# arduino-ss-usbmod-zif.net
KiCad netlist of a schematic drawn in EAGLE
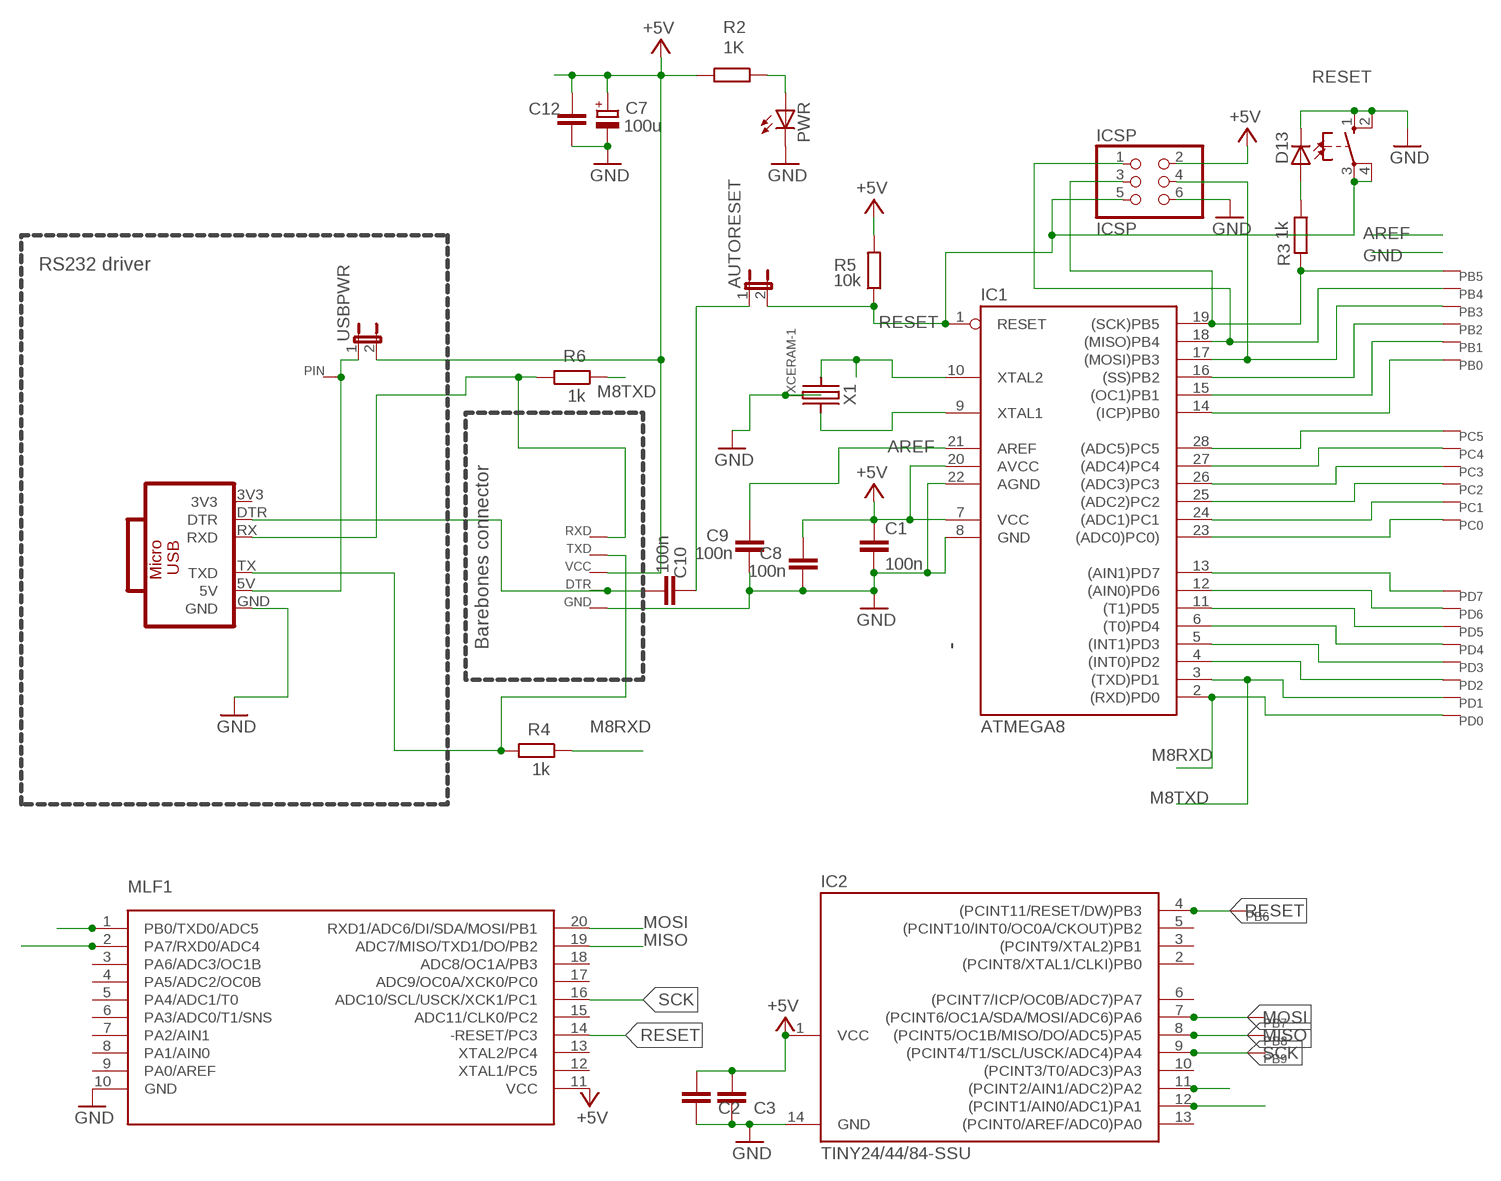
[diagram p0: schematic, sheet 1]

(export (version "E")
  (design (tool "Eeschema 10.0.6"))
  (components
    (comp (ref "AUTORESET")
      (value "JUMPER-2PTH")
      (footprint "eagle-import:1X02")
      (libsource (lib "eagle-import") (part "JUMPER-2PTH"))
    )
    (comp (ref "C1")
      (value "100n")
      (footprint "eagle-import:C050-025X075")
      (libsource (lib "eagle-import") (part "C-EU050-025X075"))
    )
    (comp (ref "C2")
      (value "100n")
      (footprint "eagle-import:C050-025X075")
      (libsource (lib "eagle-import") (part "C-EU050-025X075"))
    )
    (comp (ref "C3")
      (value "100n")
      (footprint "eagle-import:C1812")
      (libsource (lib "eagle-import") (part "C-EUC1812"))
    )
    (comp (ref "C7")
      (value "100u")
      (footprint "eagle-import:E3,5-8")
      (libsource (lib "eagle-import") (part "CPOL-EUE3.5-8"))
    )
    (comp (ref "C8")
      (value "100n")
      (footprint "eagle-import:C050-025X075")
      (libsource (lib "eagle-import") (part "C-EU050-025X075"))
    )
    (comp (ref "C9")
      (value "100n")
      (footprint "eagle-import:C050-025X075")
      (libsource (lib "eagle-import") (part "C-EU050-025X075"))
    )
    (comp (ref "C10")
      (value "100n")
      (footprint "eagle-import:C050-025X075")
      (libsource (lib "eagle-import") (part "C-EU050-025X075"))
    )
    (comp (ref "C12")
      (value "100n")
      (footprint "eagle-import:C050-025X075")
      (libsource (lib "eagle-import") (part "C-EU050-025X075"))
    )
    (comp (ref "D13")
      (value "LED3MM")
      (footprint "eagle-import:LED3MM")
      (libsource (lib "eagle-import") (part "LED3MM"))
    )
    (comp (ref "DTR")
      (value "WIRER")
      (footprint "eagle-import:GENERIC-RD-1")
      (libsource (lib "eagle-import") (part "WIRER"))
    )
    (comp (ref "GND")
      (value "WIRER")
      (footprint "eagle-import:GENERIC-RD-1")
      (libsource (lib "eagle-import") (part "WIRER"))
    )
    (comp (ref "IC1")
      (value "ATMEGA8")
      (footprint "eagle-import:ZIF28_3")
      (libsource (lib "eagle-import") (part "AT90S4433ZIF"))
    )
    (comp (ref "IC2")
      (value "TINY24/44/84-SSU")
      (footprint "eagle-import:SOIC14")
      (libsource (lib "eagle-import") (part "TINY24/44/84-SSU"))
    )
    (comp (ref "ICSP")
      (value "ICSP")
      (footprint "eagle-import:2X03")
      (libsource (lib "eagle-import") (part "PINHD-2X3"))
    )
    (comp (ref "MLF1")
      (value "ATTINY1634SOIC20")
      (footprint "eagle-import:SOIC20")
      (libsource (lib "eagle-import") (part "ATTINY1634SOIC20"))
    )
    (comp (ref "MOD1")
      (value "CH340E-MODNOHOLES")
      (footprint "eagle-import:CH340E-MOD-NOHOLES")
      (libsource (lib "eagle-import") (part "CH340E-MODNOHOLES"))
    )
    (comp (ref "PB0")
      (value "WIRE-VIA11")
      (footprint "eagle-import:VIA11")
      (libsource (lib "eagle-import") (part "WIRE-VIA11"))
    )
    (comp (ref "PB1")
      (value "WIRE-VIA11")
      (footprint "eagle-import:VIA11")
      (libsource (lib "eagle-import") (part "WIRE-VIA11"))
    )
    (comp (ref "PB2")
      (value "WIRE-VIA11")
      (footprint "eagle-import:VIA11")
      (libsource (lib "eagle-import") (part "WIRE-VIA11"))
    )
    (comp (ref "PB3")
      (value "WIRE-VIA11")
      (footprint "eagle-import:VIA11")
      (libsource (lib "eagle-import") (part "WIRE-VIA11"))
    )
    (comp (ref "PB4")
      (value "WIRE-VIA11")
      (footprint "eagle-import:VIA11")
      (libsource (lib "eagle-import") (part "WIRE-VIA11"))
    )
    (comp (ref "PB5")
      (value "WIRE-VIA11")
      (footprint "eagle-import:VIA11")
      (libsource (lib "eagle-import") (part "WIRE-VIA11"))
    )
    (comp (ref "PB6")
      (value "WIRE-VIA11")
      (footprint "eagle-import:VIA11")
      (libsource (lib "eagle-import") (part "WIRE-VIA11"))
    )
    (comp (ref "PB7")
      (value "WIRE-VIA11")
      (footprint "eagle-import:VIA11")
      (libsource (lib "eagle-import") (part "WIRE-VIA11"))
    )
    (comp (ref "PB8")
      (value "WIRE-VIA11")
      (footprint "eagle-import:VIA11")
      (libsource (lib "eagle-import") (part "WIRE-VIA11"))
    )
    (comp (ref "PB9")
      (value "WIRE-VIA11")
      (footprint "eagle-import:VIA11")
      (libsource (lib "eagle-import") (part "WIRE-VIA11"))
    )
    (comp (ref "PC0")
      (value "WIRER")
      (footprint "eagle-import:GENERIC-RD-1")
      (libsource (lib "eagle-import") (part "WIRER"))
    )
    (comp (ref "PC1")
      (value "WIRE-VIA11")
      (footprint "eagle-import:VIA11")
      (libsource (lib "eagle-import") (part "WIRE-VIA11"))
    )
    (comp (ref "PC2")
      (value "WIRE-VIA11")
      (footprint "eagle-import:VIA11")
      (libsource (lib "eagle-import") (part "WIRE-VIA11"))
    )
    (comp (ref "PC3")
      (value "WIRE-VIA11")
      (footprint "eagle-import:VIA11")
      (libsource (lib "eagle-import") (part "WIRE-VIA11"))
    )
    (comp (ref "PC4")
      (value "WIRE-VIA11")
      (footprint "eagle-import:VIA11")
      (libsource (lib "eagle-import") (part "WIRE-VIA11"))
    )
    (comp (ref "PC5")
      (value "WIRE-VIA11")
      (footprint "eagle-import:VIA11")
      (libsource (lib "eagle-import") (part "WIRE-VIA11"))
    )
    (comp (ref "PD0")
      (value "WIRE-VIA11")
      (footprint "eagle-import:VIA11")
      (libsource (lib "eagle-import") (part "WIRE-VIA11"))
    )
    (comp (ref "PD1")
      (value "WIRE-VIA11")
      (footprint "eagle-import:VIA11")
      (libsource (lib "eagle-import") (part "WIRE-VIA11"))
    )
    (comp (ref "PD2")
      (value "WIRE-VIA11")
      (footprint "eagle-import:VIA11")
      (libsource (lib "eagle-import") (part "WIRE-VIA11"))
    )
    (comp (ref "PD3")
      (value "WIRE-VIA11")
      (footprint "eagle-import:VIA11")
      (libsource (lib "eagle-import") (part "WIRE-VIA11"))
    )
    (comp (ref "PD4")
      (value "WIRE-VIA11")
      (footprint "eagle-import:VIA11")
      (libsource (lib "eagle-import") (part "WIRE-VIA11"))
    )
    (comp (ref "PD5")
      (value "WIRE-VIA11")
      (footprint "eagle-import:VIA11")
      (libsource (lib "eagle-import") (part "WIRE-VIA11"))
    )
    (comp (ref "PD6")
      (value "WIRE-VIA11")
      (footprint "eagle-import:VIA11")
      (libsource (lib "eagle-import") (part "WIRE-VIA11"))
    )
    (comp (ref "PD7")
      (value "WIRE-VIA11")
      (footprint "eagle-import:VIA11")
      (libsource (lib "eagle-import") (part "WIRE-VIA11"))
    )
    (comp (ref "PIN")
      (value "WIRER")
      (footprint "eagle-import:GENERIC-RD-1")
      (libsource (lib "eagle-import") (part "WIRER"))
    )
    (comp (ref "PWR")
      (value "LED3MM")
      (footprint "eagle-import:LED3MM")
      (libsource (lib "eagle-import") (part "LED3MM"))
    )
    (comp (ref "R2")
      (value "1K")
      (footprint "eagle-import:0207_7")
      (libsource (lib "eagle-import") (part "R-EU_0207/7"))
    )
    (comp (ref "R3")
      (value "1k")
      (footprint "eagle-import:0204_5")
      (libsource (lib "eagle-import") (part "R-EU_0204/5"))
    )
    (comp (ref "R4")
      (value "1k")
      (footprint "eagle-import:0207_7")
      (libsource (lib "eagle-import") (part "R-EU_0207/7"))
    )
    (comp (ref "R5")
      (value "10k")
      (footprint "eagle-import:0207_7")
      (libsource (lib "eagle-import") (part "R-EU_0207/7"))
    )
    (comp (ref "R6")
      (value "1k")
      (footprint "eagle-import:0207_7")
      (libsource (lib "eagle-import") (part "R-EU_0207/7"))
    )
    (comp (ref "RESET")
      (value "10-XX")
      (footprint "eagle-import:B3F-10XX")
      (libsource (lib "eagle-import") (part "10-XX"))
    )
    (comp (ref "RXD")
      (value "WIRER")
      (footprint "eagle-import:GENERIC-RD-1")
      (libsource (lib "eagle-import") (part "WIRER"))
    )
    (comp (ref "TXD")
      (value "WIRER")
      (footprint "eagle-import:GENERIC-RD-1")
      (libsource (lib "eagle-import") (part "WIRER"))
    )
    (comp (ref "USBPWR")
      (value "JUMPER-2PTH")
      (footprint "eagle-import:1X02")
      (libsource (lib "eagle-import") (part "JUMPER-2PTH"))
    )
    (comp (ref "VCC")
      (value "WIRE-VIA11")
      (footprint "eagle-import:VIA11")
      (libsource (lib "eagle-import") (part "WIRE-VIA11"))
    )
    (comp (ref "X1")
      (value "XCERAM-1")
      (footprint "eagle-import:XTAL-3")
      (libsource (lib "eagle-import") (part "XCERAM-1"))
    )
  )
  (nets
    (net (code "1") (name "+5V") (class "Default")
      (node (ref "C1") (pin "1") (pinfunction "1_1") (pintype "passive"))
      (node (ref "C12") (pin "2") (pinfunction "2_2") (pintype "passive"))
      (node (ref "C2") (pin "1") (pinfunction "1_1") (pintype "passive"))
      (node (ref "C3") (pin "1") (pinfunction "1_1") (pintype "passive"))
      (node (ref "C7") (pin "+") (pinfunction "+_+") (pintype "passive"))
      (node (ref "C8") (pin "2") (pinfunction "2_2") (pintype "passive"))
      (node (ref "IC1") (pin "20") (pinfunction "AVCC_20") (pintype "power_in"))
      (node (ref "IC1") (pin "7") (pinfunction "VCC_7") (pintype "power_in"))
      (node (ref "IC2") (pin "1") (pinfunction "VCC_1") (pintype "power_in"))
      (node (ref "ICSP") (pin "2") (pinfunction "2_2") (pintype "passive"))
      (node (ref "MLF1") (pin "11") (pinfunction "VCC_11") (pintype "power_in"))
      (node (ref "R2") (pin "2") (pinfunction "2_2") (pintype "passive"))
      (node (ref "R5") (pin "2") (pinfunction "2_2") (pintype "passive"))
      (node (ref "USBPWR") (pin "2") (pinfunction "2_2") (pintype "passive"))
      (node (ref "VCC") (pin "P$1") (pinfunction "P$1_P$1") (pintype "bidirectional"))
    )
    (net (code "2") (name "/3V3") (class "Default")
      (node (ref "MOD1") (pin "3V3") (pinfunction "3V3_3V3") (pintype "power_in"))
    )
    (net (code "3") (name "/AREF") (class "Default")
      (node (ref "C9") (pin "2") (pinfunction "2_2") (pintype "passive"))
      (node (ref "IC1") (pin "21") (pinfunction "AREF_21") (pintype "passive"))
    )
    (net (code "4") (name "/M8RXD") (class "Default")
      (node (ref "IC1") (pin "2") (pinfunction "(RXD)PD0_2") (pintype "bidirectional"))
      (node (ref "IC2") (pin "11") (pinfunction "(PCINT2/AIN1/ADC2)PA2_11") (pintype "bidirectional"))
      (node (ref "MLF1") (pin "1") (pinfunction "PB0/TXD0/ADC5_1") (pintype "bidirectional"))
      (node (ref "PD0") (pin "P$1") (pinfunction "P$1_P$1") (pintype "bidirectional"))
      (node (ref "R4") (pin "1") (pinfunction "1_1") (pintype "passive"))
    )
    (net (code "5") (name "/M8TXD") (class "Default")
      (node (ref "IC1") (pin "3") (pinfunction "(TXD)PD1_3") (pintype "bidirectional"))
      (node (ref "IC2") (pin "12") (pinfunction "(PCINT1/AIN0/ADC1)PA1_12") (pintype "bidirectional"))
      (node (ref "MLF1") (pin "2") (pinfunction "PA7/RXD0/ADC4_2") (pintype "bidirectional"))
      (node (ref "PD1") (pin "P$1") (pinfunction "P$1_P$1") (pintype "bidirectional"))
      (node (ref "R6") (pin "1") (pinfunction "1_1") (pintype "passive"))
    )
    (net (code "6") (name "GND") (class "Default")
      (node (ref "C1") (pin "2") (pinfunction "2_2") (pintype "passive"))
      (node (ref "C12") (pin "1") (pinfunction "1_1") (pintype "passive"))
      (node (ref "C2") (pin "2") (pinfunction "2_2") (pintype "passive"))
      (node (ref "C3") (pin "2") (pinfunction "2_2") (pintype "passive"))
      (node (ref "C7") (pin "-") (pinfunction "-_-") (pintype "passive"))
      (node (ref "C8") (pin "1") (pinfunction "1_1") (pintype "passive"))
      (node (ref "C9") (pin "1") (pinfunction "1_1") (pintype "passive"))
      (node (ref "D13") (pin "K") (pinfunction "C_K") (pintype "passive"))
      (node (ref "GND") (pin "P$1") (pinfunction "P$1_P$1") (pintype "bidirectional"))
      (node (ref "IC1") (pin "22") (pinfunction "AGND_22") (pintype "power_in"))
      (node (ref "IC1") (pin "8") (pinfunction "GND_8") (pintype "power_in"))
      (node (ref "IC2") (pin "14") (pinfunction "GND_14") (pintype "power_in"))
      (node (ref "ICSP") (pin "6") (pinfunction "6_6") (pintype "passive"))
      (node (ref "MLF1") (pin "10") (pinfunction "GND_10") (pintype "power_in"))
      (node (ref "MOD1") (pin "GND") (pinfunction "GND_GND") (pintype "power_in"))
      (node (ref "PWR") (pin "K") (pinfunction "C_K") (pintype "passive"))
      (node (ref "RESET") (pin "1") (pinfunction "S_1") (pintype "passive"))
      (node (ref "RESET") (pin "2") (pinfunction "S1_2") (pintype "passive"))
      (node (ref "X1") (pin "P$2") (pinfunction "GND_P$2") (pintype "passive"))
    )
    (net (code "7") (name "MISO") (class "Default")
      (node (ref "IC1") (pin "18") (pinfunction "(MISO)PB4_18") (pintype "bidirectional"))
      (node (ref "IC2") (pin "8") (pinfunction "(PCINT5/OC1B/MISO/DO/ADC5)PA5_8") (pintype "bidirectional"))
      (node (ref "ICSP") (pin "1") (pinfunction "1_1") (pintype "passive"))
      (node (ref "MLF1") (pin "19") (pinfunction "ADC7/MISO/TXD1/DO/PB2_19") (pintype "bidirectional"))
      (node (ref "PB4") (pin "P$1") (pinfunction "P$1_P$1") (pintype "bidirectional"))
      (node (ref "PB8") (pin "P$1") (pinfunction "P$1_P$1") (pintype "bidirectional"))
    )
    (net (code "8") (name "MOSI") (class "Default")
      (node (ref "IC1") (pin "17") (pinfunction "(MOSI)PB3_17") (pintype "bidirectional"))
      (node (ref "IC2") (pin "7") (pinfunction "(PCINT6/OC1A/SDA/MOSI/ADC6)PA6_7") (pintype "bidirectional"))
      (node (ref "ICSP") (pin "4") (pinfunction "4_4") (pintype "passive"))
      (node (ref "MLF1") (pin "20") (pinfunction "RXD1/ADC6/DI/SDA/MOSI/PB1_20") (pintype "bidirectional"))
      (node (ref "PB3") (pin "P$1") (pinfunction "P$1_P$1") (pintype "bidirectional"))
      (node (ref "PB7") (pin "P$1") (pinfunction "P$1_P$1") (pintype "bidirectional"))
    )
    (net (code "9") (name "Net-(AUTORESET-Pad1)") (class "Default")
      (node (ref "AUTORESET") (pin "1") (pinfunction "1_1") (pintype "passive"))
      (node (ref "C10") (pin "2") (pinfunction "2_2") (pintype "passive"))
    )
    (net (code "10") (name "Net-(C10-Pad1)") (class "Default")
      (node (ref "C10") (pin "1") (pinfunction "1_1") (pintype "passive"))
      (node (ref "DTR") (pin "P$1") (pinfunction "P$1_P$1") (pintype "bidirectional"))
      (node (ref "MOD1") (pin "DTR") (pinfunction "DTR_DTR") (pintype "output"))
    )
    (net (code "11") (name "Net-(D13-PadA)") (class "Default")
      (node (ref "D13") (pin "A") (pinfunction "A_A") (pintype "passive"))
      (node (ref "R3") (pin "1") (pinfunction "1_1") (pintype "passive"))
    )
    (net (code "12") (name "Net-(IC1-(ADC0)PC0))") (class "Default")
      (node (ref "IC1") (pin "23") (pinfunction "(ADC0)PC0)_23") (pintype "bidirectional"))
      (node (ref "PC0") (pin "P$1") (pinfunction "P$1_P$1") (pintype "bidirectional"))
    )
    (net (code "13") (name "Net-(IC1-(ADC1)PC1)") (class "Default")
      (node (ref "IC1") (pin "24") (pinfunction "(ADC1)PC1_24") (pintype "bidirectional"))
      (node (ref "PC1") (pin "P$1") (pinfunction "P$1_P$1") (pintype "bidirectional"))
    )
    (net (code "14") (name "Net-(IC1-(ADC2)PC2)") (class "Default")
      (node (ref "IC1") (pin "25") (pinfunction "(ADC2)PC2_25") (pintype "bidirectional"))
      (node (ref "PC2") (pin "P$1") (pinfunction "P$1_P$1") (pintype "bidirectional"))
    )
    (net (code "15") (name "Net-(IC1-(ADC3)PC3)") (class "Default")
      (node (ref "IC1") (pin "26") (pinfunction "(ADC3)PC3_26") (pintype "bidirectional"))
      (node (ref "PC3") (pin "P$1") (pinfunction "P$1_P$1") (pintype "bidirectional"))
    )
    (net (code "16") (name "Net-(IC1-(ADC4)PC4)") (class "Default")
      (node (ref "IC1") (pin "27") (pinfunction "(ADC4)PC4_27") (pintype "bidirectional"))
      (node (ref "PC4") (pin "P$1") (pinfunction "P$1_P$1") (pintype "bidirectional"))
    )
    (net (code "17") (name "Net-(IC1-(ADC5)PC5)") (class "Default")
      (node (ref "IC1") (pin "28") (pinfunction "(ADC5)PC5_28") (pintype "bidirectional"))
      (node (ref "PC5") (pin "P$1") (pinfunction "P$1_P$1") (pintype "bidirectional"))
    )
    (net (code "18") (name "Net-(IC1-(AIN0)PD6)") (class "Default")
      (node (ref "IC1") (pin "12") (pinfunction "(AIN0)PD6_12") (pintype "bidirectional"))
      (node (ref "PD6") (pin "P$1") (pinfunction "P$1_P$1") (pintype "bidirectional"))
    )
    (net (code "19") (name "Net-(IC1-(AIN1)PD7)") (class "Default")
      (node (ref "IC1") (pin "13") (pinfunction "(AIN1)PD7_13") (pintype "bidirectional"))
      (node (ref "PD7") (pin "P$1") (pinfunction "P$1_P$1") (pintype "bidirectional"))
    )
    (net (code "20") (name "Net-(IC1-(ICP)PB0)") (class "Default")
      (node (ref "IC1") (pin "14") (pinfunction "(ICP)PB0_14") (pintype "bidirectional"))
      (node (ref "PB0") (pin "P$1") (pinfunction "P$1_P$1") (pintype "bidirectional"))
    )
    (net (code "21") (name "Net-(IC1-(INT0)PD2)") (class "Default")
      (node (ref "IC1") (pin "4") (pinfunction "(INT0)PD2_4") (pintype "bidirectional"))
      (node (ref "PD2") (pin "P$1") (pinfunction "P$1_P$1") (pintype "bidirectional"))
    )
    (net (code "22") (name "Net-(IC1-(INT1)PD3)") (class "Default")
      (node (ref "IC1") (pin "5") (pinfunction "(INT1)PD3_5") (pintype "bidirectional"))
      (node (ref "PD3") (pin "P$1") (pinfunction "P$1_P$1") (pintype "bidirectional"))
    )
    (net (code "23") (name "Net-(IC1-(OC1)PB1)") (class "Default")
      (node (ref "IC1") (pin "15") (pinfunction "(OC1)PB1_15") (pintype "bidirectional"))
      (node (ref "PB1") (pin "P$1") (pinfunction "P$1_P$1") (pintype "bidirectional"))
    )
    (net (code "24") (name "Net-(IC1-(SS)PB2)") (class "Default")
      (node (ref "IC1") (pin "16") (pinfunction "(SS)PB2_16") (pintype "bidirectional"))
      (node (ref "PB2") (pin "P$1") (pinfunction "P$1_P$1") (pintype "bidirectional"))
    )
    (net (code "25") (name "Net-(IC1-(T0)PD4)") (class "Default")
      (node (ref "IC1") (pin "6") (pinfunction "(T0)PD4_6") (pintype "bidirectional"))
      (node (ref "PD4") (pin "P$1") (pinfunction "P$1_P$1") (pintype "bidirectional"))
    )
    (net (code "26") (name "Net-(IC1-(T1)PD5)") (class "Default")
      (node (ref "IC1") (pin "11") (pinfunction "(T1)PD5_11") (pintype "bidirectional"))
      (node (ref "PD5") (pin "P$1") (pinfunction "P$1_P$1") (pintype "bidirectional"))
    )
    (net (code "27") (name "Net-(IC1-XTAL1)") (class "Default")
      (node (ref "IC1") (pin "9") (pinfunction "XTAL1_9") (pintype "bidirectional"))
      (node (ref "X1") (pin "P$3") (pinfunction "P$1_P$3") (pintype "passive"))
    )
    (net (code "28") (name "Net-(IC1-XTAL2)") (class "Default")
      (node (ref "IC1") (pin "10") (pinfunction "XTAL2_10") (pintype "bidirectional"))
      (node (ref "X1") (pin "P$1") (pinfunction "P$2_P$1") (pintype "passive"))
    )
    (net (code "29") (name "Net-(MOD1-Pad5V)") (class "Default")
      (node (ref "MOD1") (pin "5V") (pinfunction "5V_5V") (pintype "power_in"))
      (node (ref "PIN") (pin "P$1") (pinfunction "P$1_P$1") (pintype "bidirectional"))
      (node (ref "USBPWR") (pin "1") (pinfunction "1_1") (pintype "passive"))
    )
    (net (code "30") (name "Net-(MOD1-RXD)") (class "Default")
      (node (ref "MOD1") (pin "RX") (pinfunction "RXD_RX") (pintype "input"))
      (node (ref "R6") (pin "2") (pinfunction "2_2") (pintype "passive"))
      (node (ref "RXD") (pin "P$1") (pinfunction "P$1_P$1") (pintype "bidirectional"))
    )
    (net (code "31") (name "Net-(MOD1-TXD)") (class "Default")
      (node (ref "MOD1") (pin "TX") (pinfunction "TXD_TX") (pintype "output"))
      (node (ref "R4") (pin "2") (pinfunction "2_2") (pintype "passive"))
      (node (ref "TXD") (pin "P$1") (pinfunction "P$1_P$1") (pintype "bidirectional"))
    )
    (net (code "32") (name "Net-(PWR-PadA)") (class "Default")
      (node (ref "PWR") (pin "A") (pinfunction "A_A") (pintype "passive"))
      (node (ref "R2") (pin "1") (pinfunction "1_1") (pintype "passive"))
    )
    (net (code "33") (name "RESET") (class "Default")
      (node (ref "AUTORESET") (pin "2") (pinfunction "2_2") (pintype "passive"))
      (node (ref "IC1") (pin "1") (pinfunction "RESET_1") (pintype "input"))
      (node (ref "IC2") (pin "4") (pinfunction "(PCINT11/RESET/DW)PB3_4") (pintype "bidirectional"))
      (node (ref "ICSP") (pin "5") (pinfunction "5_5") (pintype "passive"))
      (node (ref "MLF1") (pin "14") (pinfunction "-RESET/PC3_14") (pintype "bidirectional"))
      (node (ref "PB6") (pin "P$1") (pinfunction "P$1_P$1") (pintype "bidirectional"))
      (node (ref "R5") (pin "1") (pinfunction "1_1") (pintype "passive"))
      (node (ref "RESET") (pin "3") (pinfunction "P_3") (pintype "passive"))
      (node (ref "RESET") (pin "4") (pinfunction "P1_4") (pintype "passive"))
    )
    (net (code "34") (name "SCK") (class "Default")
      (node (ref "IC1") (pin "19") (pinfunction "(SCK)PB5_19") (pintype "bidirectional"))
      (node (ref "IC2") (pin "9") (pinfunction "(PCINT4/T1/SCL/USCK/ADC4)PA4_9") (pintype "bidirectional"))
      (node (ref "ICSP") (pin "3") (pinfunction "3_3") (pintype "passive"))
      (node (ref "MLF1") (pin "16") (pinfunction "ADC10/SCL/USCK/XCK1/PC1_16") (pintype "bidirectional"))
      (node (ref "PB5") (pin "P$1") (pinfunction "P$1_P$1") (pintype "bidirectional"))
      (node (ref "PB9") (pin "P$1") (pinfunction "P$1_P$1") (pintype "bidirectional"))
      (node (ref "R3") (pin "2") (pinfunction "2_2") (pintype "passive"))
    )
    (net (code "35") (name "unconnected-(IC2-(PCINT0{slash}AREF{slash}ADC0)PA0-Pad13)") (class "Default")
      (node (ref "IC2") (pin "13") (pinfunction "(PCINT0/AREF/ADC0)PA0_13") (pintype "bidirectional"))
    )
    (net (code "36") (name "unconnected-(IC2-(PCINT3{slash}T0{slash}ADC3)PA3-Pad10)") (class "Default")
      (node (ref "IC2") (pin "10") (pinfunction "(PCINT3/T0/ADC3)PA3_10") (pintype "bidirectional"))
    )
    (net (code "37") (name "unconnected-(IC2-(PCINT7{slash}ICP{slash}OC0B{slash}ADC7)PA7-Pad6)") (class "Default")
      (node (ref "IC2") (pin "6") (pinfunction "(PCINT7/ICP/OC0B/ADC7)PA7_6") (pintype "bidirectional"))
    )
    (net (code "38") (name "unconnected-(IC2-(PCINT8{slash}XTAL1{slash}CLKI)PB0-Pad2)") (class "Default")
      (node (ref "IC2") (pin "2") (pinfunction "(PCINT8/XTAL1/CLKI)PB0_2") (pintype "bidirectional"))
    )
    (net (code "39") (name "unconnected-(IC2-(PCINT9{slash}XTAL2)PB1-Pad3)") (class "Default")
      (node (ref "IC2") (pin "3") (pinfunction "(PCINT9/XTAL2)PB1_3") (pintype "bidirectional"))
    )
    (net (code "40") (name "unconnected-(IC2-(PCINT10{slash}INT0{slash}OC0A{slash}CKOUT)PB2-Pad5)") (class "Default")
      (node (ref "IC2") (pin "5") (pinfunction "(PCINT10/INT0/OC0A/CKOUT)PB2_5") (pintype "bidirectional"))
    )
    (net (code "41") (name "unconnected-(MLF1-ADC8{slash}OC1A{slash}PB3-Pad18)") (class "Default")
      (node (ref "MLF1") (pin "18") (pinfunction "ADC8/OC1A/PB3_18") (pintype "bidirectional"))
    )
    (net (code "42") (name "unconnected-(MLF1-ADC9{slash}OC0A{slash}XCK0{slash}PC0-Pad17)") (class "Default")
      (node (ref "MLF1") (pin "17") (pinfunction "ADC9/OC0A/XCK0/PC0_17") (pintype "bidirectional"))
    )
    (net (code "43") (name "unconnected-(MLF1-ADC11{slash}CLK0{slash}PC2-Pad15)") (class "Default")
      (node (ref "MLF1") (pin "15") (pinfunction "ADC11/CLK0/PC2_15") (pintype "bidirectional"))
    )
    (net (code "44") (name "unconnected-(MLF1-PA0{slash}AREF-Pad9)") (class "Default")
      (node (ref "MLF1") (pin "9") (pinfunction "PA0/AREF_9") (pintype "bidirectional"))
    )
    (net (code "45") (name "unconnected-(MLF1-PA1{slash}AIN0-Pad8)") (class "Default")
      (node (ref "MLF1") (pin "8") (pinfunction "PA1/AIN0_8") (pintype "bidirectional"))
    )
    (net (code "46") (name "unconnected-(MLF1-PA2{slash}AIN1-Pad7)") (class "Default")
      (node (ref "MLF1") (pin "7") (pinfunction "PA2/AIN1_7") (pintype "bidirectional"))
    )
    (net (code "47") (name "unconnected-(MLF1-PA3{slash}ADC0{slash}T1{slash}SNS-Pad6)") (class "Default")
      (node (ref "MLF1") (pin "6") (pinfunction "PA3/ADC0/T1/SNS_6") (pintype "bidirectional"))
    )
    (net (code "48") (name "unconnected-(MLF1-PA4{slash}ADC1{slash}T0-Pad5)") (class "Default")
      (node (ref "MLF1") (pin "5") (pinfunction "PA4/ADC1/T0_5") (pintype "bidirectional"))
    )
    (net (code "49") (name "unconnected-(MLF1-PA5{slash}ADC2{slash}OC0B-Pad4)") (class "Default")
      (node (ref "MLF1") (pin "4") (pinfunction "PA5/ADC2/OC0B_4") (pintype "bidirectional"))
    )
    (net (code "50") (name "unconnected-(MLF1-PA6{slash}ADC3{slash}OC1B-Pad3)") (class "Default")
      (node (ref "MLF1") (pin "3") (pinfunction "PA6/ADC3/OC1B_3") (pintype "bidirectional"))
    )
    (net (code "51") (name "unconnected-(MLF1-XTAL1{slash}PC5-Pad12)") (class "Default")
      (node (ref "MLF1") (pin "12") (pinfunction "XTAL1/PC5_12") (pintype "bidirectional"))
    )
    (net (code "52") (name "unconnected-(MLF1-XTAL2{slash}PC4-Pad13)") (class "Default")
      (node (ref "MLF1") (pin "13") (pinfunction "XTAL2/PC4_13") (pintype "bidirectional"))
    )
  )
)
